# OSV-UserInterface.net
KiCad netlist of a schematic drawn in Altium Designer
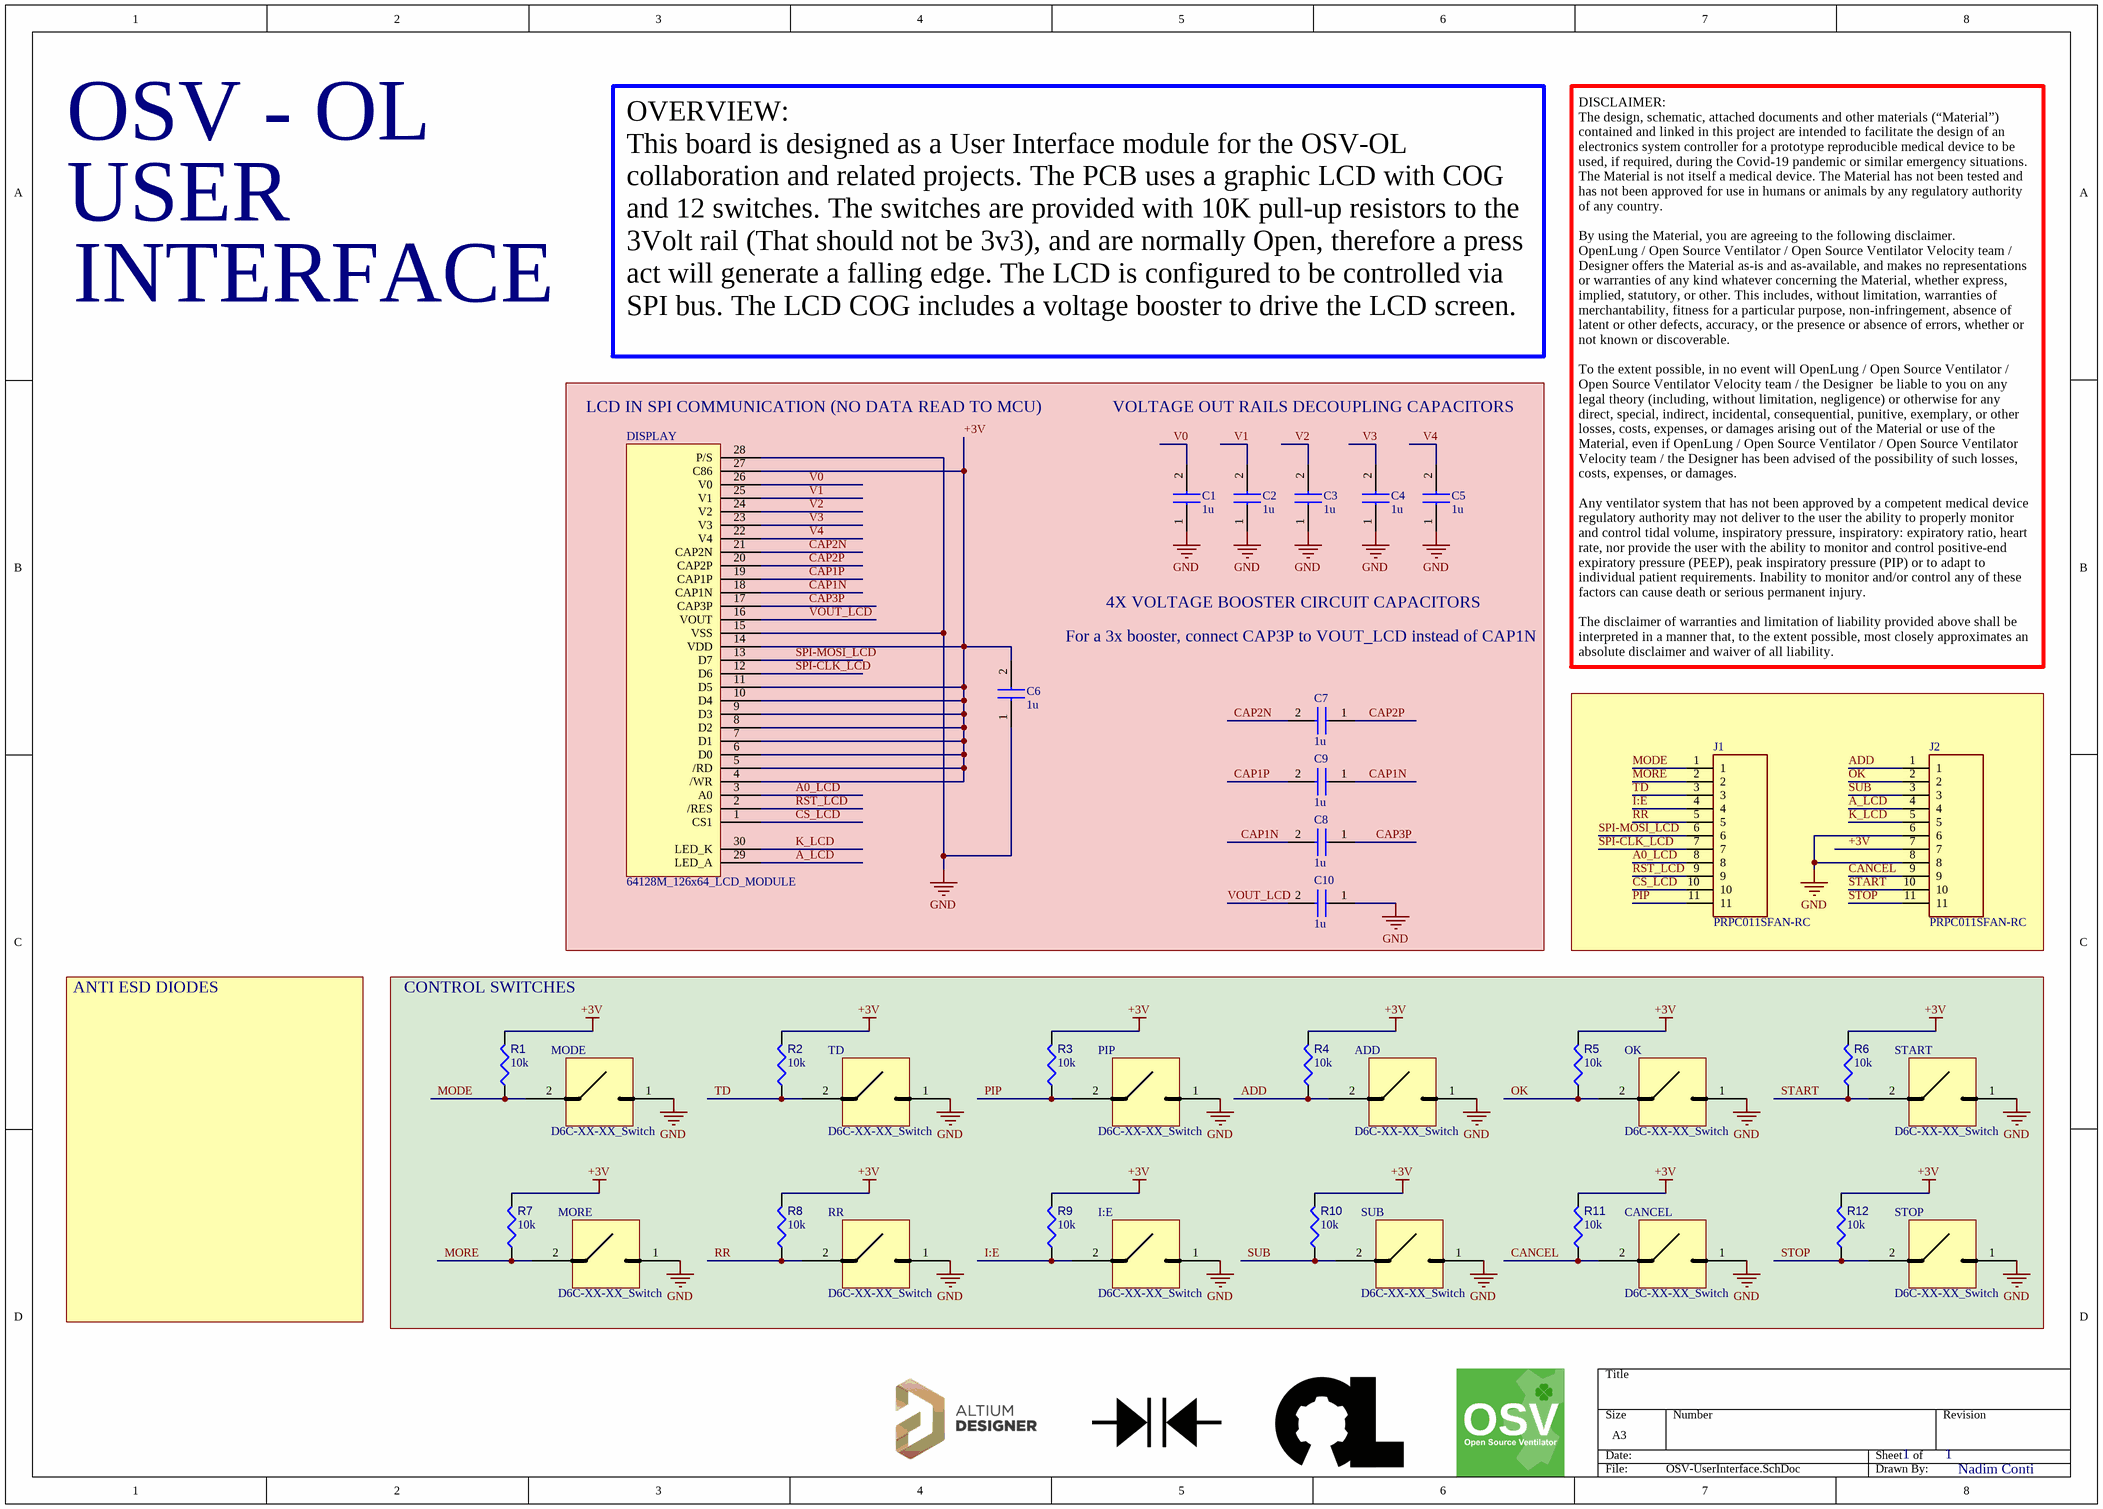
[diagram p0: OSV-UserInterface.SchDoc]

(export (version "E")
  (design (tool "Eeschema 10.0.6"))
  (components
    (comp (ref "ADD")
      (value "D6C-XX-XX_Switch")
      (footprint "D6C-60-F1_Blue-Switch")
      (libsource (lib "64128M_lcd") (part "D6C-XX-XX_Switch"))
    )
    (comp (ref "C1")
      (value "GCM21BR71H105KA03K")
      (footprint "SamacSys:CAPC2012X140N")
      (description "Capacitor")
      (fields (field (name "MOUSER PART NUMBER") "81-GCM21BR71H105KA3K") (field (name "CAPACITANCE") "1u"))
      (libsource (lib "*") (part "GCM21BR71H105KA03K"))
    )
    (comp (ref "C2")
      (value "GCM21BR71H105KA03K")
      (footprint "SamacSys:CAPC2012X140N")
      (description "Capacitor")
      (fields (field (name "MOUSER PART NUMBER") "81-GCM21BR71H105KA3K") (field (name "CAPACITANCE") "1u"))
      (libsource (lib "*") (part "GCM21BR71H105KA03K"))
    )
    (comp (ref "C3")
      (value "GCM21BR71H105KA03K")
      (footprint "SamacSys:CAPC2012X140N")
      (description "Capacitor")
      (fields (field (name "MOUSER PART NUMBER") "81-GCM21BR71H105KA3K") (field (name "CAPACITANCE") "1u"))
      (libsource (lib "*") (part "GCM21BR71H105KA03K"))
    )
    (comp (ref "C4")
      (value "GCM21BR71H105KA03K")
      (footprint "SamacSys:CAPC2012X140N")
      (description "Capacitor")
      (fields (field (name "MOUSER PART NUMBER") "81-GCM21BR71H105KA3K") (field (name "CAPACITANCE") "1u"))
      (libsource (lib "*") (part "GCM21BR71H105KA03K"))
    )
    (comp (ref "C5")
      (value "GCM21BR71H105KA03K")
      (footprint "SamacSys:CAPC2012X140N")
      (description "Capacitor")
      (fields (field (name "MOUSER PART NUMBER") "81-GCM21BR71H105KA3K") (field (name "CAPACITANCE") "1u"))
      (libsource (lib "*") (part "GCM21BR71H105KA03K"))
    )
    (comp (ref "C6")
      (value "GCM21BR71H105KA03K")
      (footprint "SamacSys:CAPC2012X140N")
      (description "Capacitor")
      (fields (field (name "MOUSER PART NUMBER") "81-GCM21BR71H105KA3K") (field (name "CAPACITANCE") "1u"))
      (libsource (lib "*") (part "GCM21BR71H105KA03K"))
    )
    (comp (ref "C7")
      (value "GCM21BR71H105KA03K")
      (footprint "SamacSys:CAPC2012X140N")
      (description "Capacitor")
      (fields (field (name "MOUSER PART NUMBER") "81-GCM21BR71H105KA3K") (field (name "CAPACITANCE") "1u"))
      (libsource (lib "*") (part "GCM21BR71H105KA03K"))
    )
    (comp (ref "C8")
      (value "GCM21BR71H105KA03K")
      (footprint "SamacSys:CAPC2012X140N")
      (description "Capacitor")
      (fields (field (name "MOUSER PART NUMBER") "81-GCM21BR71H105KA3K") (field (name "CAPACITANCE") "1u"))
      (libsource (lib "*") (part "GCM21BR71H105KA03K"))
    )
    (comp (ref "C9")
      (value "GCM21BR71H105KA03K")
      (footprint "SamacSys:CAPC2012X140N")
      (description "Capacitor")
      (fields (field (name "MOUSER PART NUMBER") "81-GCM21BR71H105KA3K") (field (name "CAPACITANCE") "1u"))
      (libsource (lib "*") (part "GCM21BR71H105KA03K"))
    )
    (comp (ref "C10")
      (value "GCM21BR71H105KA03K")
      (footprint "SamacSys:CAPC2012X140N")
      (description "Capacitor")
      (fields (field (name "MOUSER PART NUMBER") "81-GCM21BR71H105KA3K") (field (name "CAPACITANCE") "1u"))
      (libsource (lib "*") (part "GCM21BR71H105KA03K"))
    )
    (comp (ref "CANCEL")
      (value "D6C-XX-XX_Switch")
      (footprint "D6C-30-F1_YELLOW-SWITCH")
      (libsource (lib "64128M_lcd") (part "D6C-XX-XX_Switch"))
    )
    (comp (ref "DISPLAY")
      (value "64128M_126x64_LCD_MODULE")
      (footprint "64128M_LCD")
      (description "64128M Series LCD Module (128 x 64 DOTS)")
      (libsource (lib "64128M_lcd") (part "64128M_126x64_LCD_MODULE"))
    )
    (comp (ref "I:E")
      (value "D6C-XX-XX_Switch")
      (footprint "D6C-00-F1_White-Switch")
      (libsource (lib "64128M_lcd") (part "D6C-XX-XX_Switch"))
    )
    (comp (ref "J1")
      (value "PRPC011SFAN-RC")
      (footprint "SamacSys:HDRV11W64P254_1X11_2794X254X1058P")
      (description "Connector")
      (libsource (lib "*") (part "PRPC011SFAN-RC"))
    )
    (comp (ref "J2")
      (value "PRPC011SFAN-RC")
      (footprint "SamacSys:HDRV11W64P254_1X11_2794X254X1058P")
      (description "Connector")
      (libsource (lib "*") (part "PRPC011SFAN-RC"))
    )
    (comp (ref "MODE")
      (value "D6C-XX-XX_Switch")
      (footprint "D6C-30-F1_YELLOW-SWITCH")
      (libsource (lib "64128M_lcd") (part "D6C-XX-XX_Switch"))
    )
    (comp (ref "MORE")
      (value "D6C-XX-XX_Switch")
      (footprint "D6C-00-F1_White-Switch")
      (libsource (lib "64128M_lcd") (part "D6C-XX-XX_Switch"))
    )
    (comp (ref "OK")
      (value "D6C-XX-XX_Switch")
      (footprint "D6C-50-F1_GREEN-Switch")
      (libsource (lib "64128M_lcd") (part "D6C-XX-XX_Switch"))
    )
    (comp (ref "PIP")
      (value "D6C-XX-XX_Switch")
      (footprint "D6C-00-F1_White-Switch")
      (libsource (lib "64128M_lcd") (part "D6C-XX-XX_Switch"))
    )
    (comp (ref "R1")
      (value "10k")
      (footprint "RESC2013X50X35ML15T15")
      (description "Chip Resistor, 10 KOhm, +/- 1%, 125 mW, -55 to 155 degC, 0805 (2012 Metric)")
      (fields (field (name "POWER") "125mW") (field (name "TOLERANCE") "1%"))
      (libsource (lib "Altium Concord Pro on A365") (part "RES-2"))
    )
    (comp (ref "R2")
      (value "10k")
      (footprint "RESC2013X50X35ML15T15")
      (description "Chip Resistor, 10 KOhm, +/- 1%, 125 mW, -55 to 155 degC, 0805 (2012 Metric)")
      (fields (field (name "POWER") "125mW") (field (name "TOLERANCE") "1%"))
      (libsource (lib "Altium Concord Pro on A365") (part "RES-2"))
    )
    (comp (ref "R3")
      (value "10k")
      (footprint "RESC2013X50X35ML15T15")
      (description "Chip Resistor, 10 KOhm, +/- 1%, 125 mW, -55 to 155 degC, 0805 (2012 Metric)")
      (fields (field (name "POWER") "125mW") (field (name "TOLERANCE") "1%"))
      (libsource (lib "Altium Concord Pro on A365") (part "RES-2"))
    )
    (comp (ref "R4")
      (value "10k")
      (footprint "RESC2013X50X35ML15T15")
      (description "Chip Resistor, 10 KOhm, +/- 1%, 125 mW, -55 to 155 degC, 0805 (2012 Metric)")
      (fields (field (name "POWER") "125mW") (field (name "TOLERANCE") "1%"))
      (libsource (lib "Altium Concord Pro on A365") (part "RES-2"))
    )
    (comp (ref "R5")
      (value "10k")
      (footprint "RESC2013X50X35ML15T15")
      (description "Chip Resistor, 10 KOhm, +/- 1%, 125 mW, -55 to 155 degC, 0805 (2012 Metric)")
      (fields (field (name "POWER") "125mW") (field (name "TOLERANCE") "1%"))
      (libsource (lib "Altium Concord Pro on A365") (part "RES-2"))
    )
    (comp (ref "R6")
      (value "10k")
      (footprint "RESC2013X50X35ML15T15")
      (description "Chip Resistor, 10 KOhm, +/- 1%, 125 mW, -55 to 155 degC, 0805 (2012 Metric)")
      (fields (field (name "POWER") "125mW") (field (name "TOLERANCE") "1%"))
      (libsource (lib "Altium Concord Pro on A365") (part "RES-2"))
    )
    (comp (ref "R7")
      (value "10k")
      (footprint "RESC2013X50X35ML15T15")
      (description "Chip Resistor, 10 KOhm, +/- 1%, 125 mW, -55 to 155 degC, 0805 (2012 Metric)")
      (fields (field (name "POWER") "125mW") (field (name "TOLERANCE") "1%"))
      (libsource (lib "Altium Concord Pro on A365") (part "RES-2"))
    )
    (comp (ref "R8")
      (value "10k")
      (footprint "RESC2013X50X35ML15T15")
      (description "Chip Resistor, 10 KOhm, +/- 1%, 125 mW, -55 to 155 degC, 0805 (2012 Metric)")
      (fields (field (name "POWER") "125mW") (field (name "TOLERANCE") "1%"))
      (libsource (lib "Altium Concord Pro on A365") (part "RES-2"))
    )
    (comp (ref "R9")
      (value "10k")
      (footprint "RESC2013X50X35ML15T15")
      (description "Chip Resistor, 10 KOhm, +/- 1%, 125 mW, -55 to 155 degC, 0805 (2012 Metric)")
      (fields (field (name "POWER") "125mW") (field (name "TOLERANCE") "1%"))
      (libsource (lib "Altium Concord Pro on A365") (part "RES-2"))
    )
    (comp (ref "R10")
      (value "10k")
      (footprint "RESC2013X50X35ML15T15")
      (description "Chip Resistor, 10 KOhm, +/- 1%, 125 mW, -55 to 155 degC, 0805 (2012 Metric)")
      (fields (field (name "POWER") "125mW") (field (name "TOLERANCE") "1%"))
      (libsource (lib "Altium Concord Pro on A365") (part "RES-2"))
    )
    (comp (ref "R11")
      (value "10k")
      (footprint "RESC2013X50X35ML15T15")
      (description "Chip Resistor, 10 KOhm, +/- 1%, 125 mW, -55 to 155 degC, 0805 (2012 Metric)")
      (fields (field (name "POWER") "125mW") (field (name "TOLERANCE") "1%"))
      (libsource (lib "Altium Concord Pro on A365") (part "RES-2"))
    )
    (comp (ref "R12")
      (value "10k")
      (footprint "RESC2013X50X35ML15T15")
      (description "Chip Resistor, 10 KOhm, +/- 1%, 125 mW, -55 to 155 degC, 0805 (2012 Metric)")
      (fields (field (name "POWER") "125mW") (field (name "TOLERANCE") "1%"))
      (libsource (lib "Altium Concord Pro on A365") (part "RES-2"))
    )
    (comp (ref "RR")
      (value "D6C-XX-XX_Switch")
      (footprint "D6C-00-F1_White-Switch")
      (libsource (lib "64128M_lcd") (part "D6C-XX-XX_Switch"))
    )
    (comp (ref "START")
      (value "D6C-XX-XX_Switch")
      (footprint "D6C-50-F1_GREEN-Switch")
      (libsource (lib "64128M_lcd") (part "D6C-XX-XX_Switch"))
    )
    (comp (ref "STOP")
      (value "D6C-XX-XX_Switch")
      (footprint "D6C-40-F1_RED-SWITCH")
      (libsource (lib "64128M_lcd") (part "D6C-XX-XX_Switch"))
    )
    (comp (ref "SUB")
      (value "D6C-XX-XX_Switch")
      (footprint "D6C-60-F1_Blue-Switch")
      (libsource (lib "64128M_lcd") (part "D6C-XX-XX_Switch"))
    )
    (comp (ref "TD")
      (value "D6C-XX-XX_Switch")
      (footprint "D6C-00-F1_White-Switch")
      (libsource (lib "64128M_lcd") (part "D6C-XX-XX_Switch"))
    )
  )
  (nets
    (net (code "1") (name "+3V") (class "Default")
      (node (ref "C6") (pin "2") (pinfunction "2_2") (pintype "passive"))
      (node (ref "DISPLAY") (pin "10") (pinfunction "D4_10") (pintype "passive"))
      (node (ref "DISPLAY") (pin "11") (pinfunction "D5_11") (pintype "passive"))
      (node (ref "DISPLAY") (pin "14") (pinfunction "VDD_14") (pintype "passive"))
      (node (ref "DISPLAY") (pin "27") (pinfunction "C86_27") (pintype "passive"))
      (node (ref "DISPLAY") (pin "4") (pinfunction "/WR_4") (pintype "passive"))
      (node (ref "DISPLAY") (pin "5") (pinfunction "/RD_5") (pintype "passive"))
      (node (ref "DISPLAY") (pin "6") (pinfunction "D0_6") (pintype "passive"))
      (node (ref "DISPLAY") (pin "7") (pinfunction "D1_7") (pintype "passive"))
      (node (ref "DISPLAY") (pin "8") (pinfunction "D2_8") (pintype "passive"))
      (node (ref "DISPLAY") (pin "9") (pinfunction "D3_9") (pintype "passive"))
      (node (ref "J2") (pin "7") (pinfunction "7_7") (pintype "passive"))
      (node (ref "R1") (pin "2") (pinfunction "2_2") (pintype "passive"))
      (node (ref "R10") (pin "2") (pinfunction "2_2") (pintype "passive"))
      (node (ref "R11") (pin "2") (pinfunction "2_2") (pintype "passive"))
      (node (ref "R12") (pin "2") (pinfunction "2_2") (pintype "passive"))
      (node (ref "R2") (pin "2") (pinfunction "2_2") (pintype "passive"))
      (node (ref "R3") (pin "2") (pinfunction "2_2") (pintype "passive"))
      (node (ref "R4") (pin "2") (pinfunction "2_2") (pintype "passive"))
      (node (ref "R5") (pin "2") (pinfunction "2_2") (pintype "passive"))
      (node (ref "R6") (pin "2") (pinfunction "2_2") (pintype "passive"))
      (node (ref "R7") (pin "2") (pinfunction "2_2") (pintype "passive"))
      (node (ref "R8") (pin "2") (pinfunction "2_2") (pintype "passive"))
      (node (ref "R9") (pin "2") (pinfunction "2_2") (pintype "passive"))
    )
    (net (code "2") (name "/A0_LCD") (class "Default")
      (node (ref "DISPLAY") (pin "3") (pinfunction "A0_3") (pintype "passive"))
      (node (ref "J1") (pin "8") (pinfunction "8_8") (pintype "passive"))
    )
    (net (code "3") (name "/ADD") (class "Default")
      (node (ref "ADD") (pin "2") (pintype "passive"))
      (node (ref "J2") (pin "1") (pinfunction "1_1") (pintype "passive"))
      (node (ref "R4") (pin "1") (pinfunction "1_1") (pintype "passive"))
    )
    (net (code "4") (name "/A_LCD") (class "Default")
      (node (ref "DISPLAY") (pin "29") (pinfunction "LED_A_29") (pintype "passive"))
      (node (ref "J2") (pin "4") (pinfunction "4_4") (pintype "passive"))
    )
    (net (code "5") (name "/CANCEL") (class "Default")
      (node (ref "CANCEL") (pin "2") (pintype "passive"))
      (node (ref "J2") (pin "9") (pinfunction "9_9") (pintype "passive"))
      (node (ref "R11") (pin "1") (pinfunction "1_1") (pintype "passive"))
    )
    (net (code "6") (name "/CAP1N") (class "Default")
      (node (ref "C8") (pin "2") (pinfunction "2_2") (pintype "passive"))
      (node (ref "C9") (pin "1") (pinfunction "1_1") (pintype "passive"))
      (node (ref "DISPLAY") (pin "18") (pinfunction "CAP1N_18") (pintype "passive"))
    )
    (net (code "7") (name "/CAP1P") (class "Default")
      (node (ref "C9") (pin "2") (pinfunction "2_2") (pintype "passive"))
      (node (ref "DISPLAY") (pin "19") (pinfunction "CAP1P_19") (pintype "passive"))
    )
    (net (code "8") (name "/CAP2N") (class "Default")
      (node (ref "C7") (pin "2") (pinfunction "2_2") (pintype "passive"))
      (node (ref "DISPLAY") (pin "21") (pinfunction "CAP2N_21") (pintype "passive"))
    )
    (net (code "9") (name "/CAP2P") (class "Default")
      (node (ref "C7") (pin "1") (pinfunction "1_1") (pintype "passive"))
      (node (ref "DISPLAY") (pin "20") (pinfunction "CAP2P_20") (pintype "passive"))
    )
    (net (code "10") (name "/CAP3P") (class "Default")
      (node (ref "C8") (pin "1") (pinfunction "1_1") (pintype "passive"))
      (node (ref "DISPLAY") (pin "17") (pinfunction "CAP3P_17") (pintype "passive"))
    )
    (net (code "11") (name "/CS_LCD") (class "Default")
      (node (ref "DISPLAY") (pin "1") (pinfunction "CS1_1") (pintype "passive"))
      (node (ref "J1") (pin "10") (pinfunction "10_10") (pintype "passive"))
    )
    (net (code "12") (name "/I:E") (class "Default")
      (node (ref "I:E") (pin "2") (pintype "passive"))
      (node (ref "J1") (pin "4") (pinfunction "4_4") (pintype "passive"))
      (node (ref "R9") (pin "1") (pinfunction "1_1") (pintype "passive"))
    )
    (net (code "13") (name "/K_LCD") (class "Default")
      (node (ref "DISPLAY") (pin "30") (pinfunction "LED_K_30") (pintype "passive"))
      (node (ref "J2") (pin "5") (pinfunction "5_5") (pintype "passive"))
    )
    (net (code "14") (name "/MODE") (class "Default")
      (node (ref "J1") (pin "1") (pinfunction "1_1") (pintype "passive"))
      (node (ref "MODE") (pin "2") (pintype "passive"))
      (node (ref "R1") (pin "1") (pinfunction "1_1") (pintype "passive"))
    )
    (net (code "15") (name "/MORE") (class "Default")
      (node (ref "J1") (pin "2") (pinfunction "2_2") (pintype "passive"))
      (node (ref "MORE") (pin "2") (pintype "passive"))
      (node (ref "R7") (pin "1") (pinfunction "1_1") (pintype "passive"))
    )
    (net (code "16") (name "/OK") (class "Default")
      (node (ref "J2") (pin "2") (pinfunction "2_2") (pintype "passive"))
      (node (ref "OK") (pin "2") (pintype "passive"))
      (node (ref "R5") (pin "1") (pinfunction "1_1") (pintype "passive"))
    )
    (net (code "17") (name "/PIP") (class "Default")
      (node (ref "J1") (pin "11") (pinfunction "11_11") (pintype "passive"))
      (node (ref "PIP") (pin "2") (pintype "passive"))
      (node (ref "R3") (pin "1") (pinfunction "1_1") (pintype "passive"))
    )
    (net (code "18") (name "/RR") (class "Default")
      (node (ref "J1") (pin "5") (pinfunction "5_5") (pintype "passive"))
      (node (ref "R8") (pin "1") (pinfunction "1_1") (pintype "passive"))
      (node (ref "RR") (pin "2") (pintype "passive"))
    )
    (net (code "19") (name "/RST_LCD") (class "Default")
      (node (ref "DISPLAY") (pin "2") (pinfunction "/RES_2") (pintype "passive"))
      (node (ref "J1") (pin "9") (pinfunction "9_9") (pintype "passive"))
    )
    (net (code "20") (name "/SPI-CLK_LCD") (class "Default")
      (node (ref "DISPLAY") (pin "12") (pinfunction "D6_12") (pintype "passive"))
      (node (ref "J1") (pin "7") (pinfunction "7_7") (pintype "passive"))
    )
    (net (code "21") (name "/SPI-MOSI_LCD") (class "Default")
      (node (ref "DISPLAY") (pin "13") (pinfunction "D7_13") (pintype "passive"))
      (node (ref "J1") (pin "6") (pinfunction "6_6") (pintype "passive"))
    )
    (net (code "22") (name "/START") (class "Default")
      (node (ref "J2") (pin "10") (pinfunction "10_10") (pintype "passive"))
      (node (ref "R6") (pin "1") (pinfunction "1_1") (pintype "passive"))
      (node (ref "START") (pin "2") (pintype "passive"))
    )
    (net (code "23") (name "/STOP") (class "Default")
      (node (ref "J2") (pin "11") (pinfunction "11_11") (pintype "passive"))
      (node (ref "R12") (pin "1") (pinfunction "1_1") (pintype "passive"))
      (node (ref "STOP") (pin "2") (pintype "passive"))
    )
    (net (code "24") (name "/SUB") (class "Default")
      (node (ref "J2") (pin "3") (pinfunction "3_3") (pintype "passive"))
      (node (ref "R10") (pin "1") (pinfunction "1_1") (pintype "passive"))
      (node (ref "SUB") (pin "2") (pintype "passive"))
    )
    (net (code "25") (name "/TD") (class "Default")
      (node (ref "J1") (pin "3") (pinfunction "3_3") (pintype "passive"))
      (node (ref "R2") (pin "1") (pinfunction "1_1") (pintype "passive"))
      (node (ref "TD") (pin "2") (pintype "passive"))
    )
    (net (code "26") (name "/V0") (class "Default")
      (node (ref "C1") (pin "2") (pinfunction "2_2") (pintype "passive"))
      (node (ref "DISPLAY") (pin "26") (pinfunction "V0_26") (pintype "passive"))
    )
    (net (code "27") (name "/V1") (class "Default")
      (node (ref "C2") (pin "2") (pinfunction "2_2") (pintype "passive"))
      (node (ref "DISPLAY") (pin "25") (pinfunction "V1_25") (pintype "passive"))
    )
    (net (code "28") (name "/V2") (class "Default")
      (node (ref "C3") (pin "2") (pinfunction "2_2") (pintype "passive"))
      (node (ref "DISPLAY") (pin "24") (pinfunction "V2_24") (pintype "passive"))
    )
    (net (code "29") (name "/V3") (class "Default")
      (node (ref "C4") (pin "2") (pinfunction "2_2") (pintype "passive"))
      (node (ref "DISPLAY") (pin "23") (pinfunction "V3_23") (pintype "passive"))
    )
    (net (code "30") (name "/V4") (class "Default")
      (node (ref "C5") (pin "2") (pinfunction "2_2") (pintype "passive"))
      (node (ref "DISPLAY") (pin "22") (pinfunction "V4_22") (pintype "passive"))
    )
    (net (code "31") (name "/VOUT_LCD") (class "Default")
      (node (ref "C10") (pin "2") (pinfunction "2_2") (pintype "passive"))
      (node (ref "DISPLAY") (pin "16") (pinfunction "VOUT_16") (pintype "passive"))
    )
    (net (code "32") (name "GND") (class "Default")
      (node (ref "ADD") (pin "1") (pintype "passive"))
      (node (ref "C1") (pin "1") (pinfunction "1_1") (pintype "passive"))
      (node (ref "C10") (pin "1") (pinfunction "1_1") (pintype "passive"))
      (node (ref "C2") (pin "1") (pinfunction "1_1") (pintype "passive"))
      (node (ref "C3") (pin "1") (pinfunction "1_1") (pintype "passive"))
      (node (ref "C4") (pin "1") (pinfunction "1_1") (pintype "passive"))
      (node (ref "C5") (pin "1") (pinfunction "1_1") (pintype "passive"))
      (node (ref "C6") (pin "1") (pinfunction "1_1") (pintype "passive"))
      (node (ref "CANCEL") (pin "1") (pintype "passive"))
      (node (ref "DISPLAY") (pin "15") (pinfunction "VSS_15") (pintype "passive"))
      (node (ref "DISPLAY") (pin "28") (pinfunction "P/S_28") (pintype "passive"))
      (node (ref "I:E") (pin "1") (pintype "passive"))
      (node (ref "J2") (pin "6") (pinfunction "6_6") (pintype "passive"))
      (node (ref "J2") (pin "8") (pinfunction "8_8") (pintype "passive"))
      (node (ref "MODE") (pin "1") (pintype "passive"))
      (node (ref "MORE") (pin "1") (pintype "passive"))
      (node (ref "OK") (pin "1") (pintype "passive"))
      (node (ref "PIP") (pin "1") (pintype "passive"))
      (node (ref "RR") (pin "1") (pintype "passive"))
      (node (ref "START") (pin "1") (pintype "passive"))
      (node (ref "STOP") (pin "1") (pintype "passive"))
      (node (ref "SUB") (pin "1") (pintype "passive"))
      (node (ref "TD") (pin "1") (pintype "passive"))
    )
  )
)
